# SLRC_2019_Robot_PCB_Schematic.net
KiCad netlist of a schematic drawn in Altium Designer
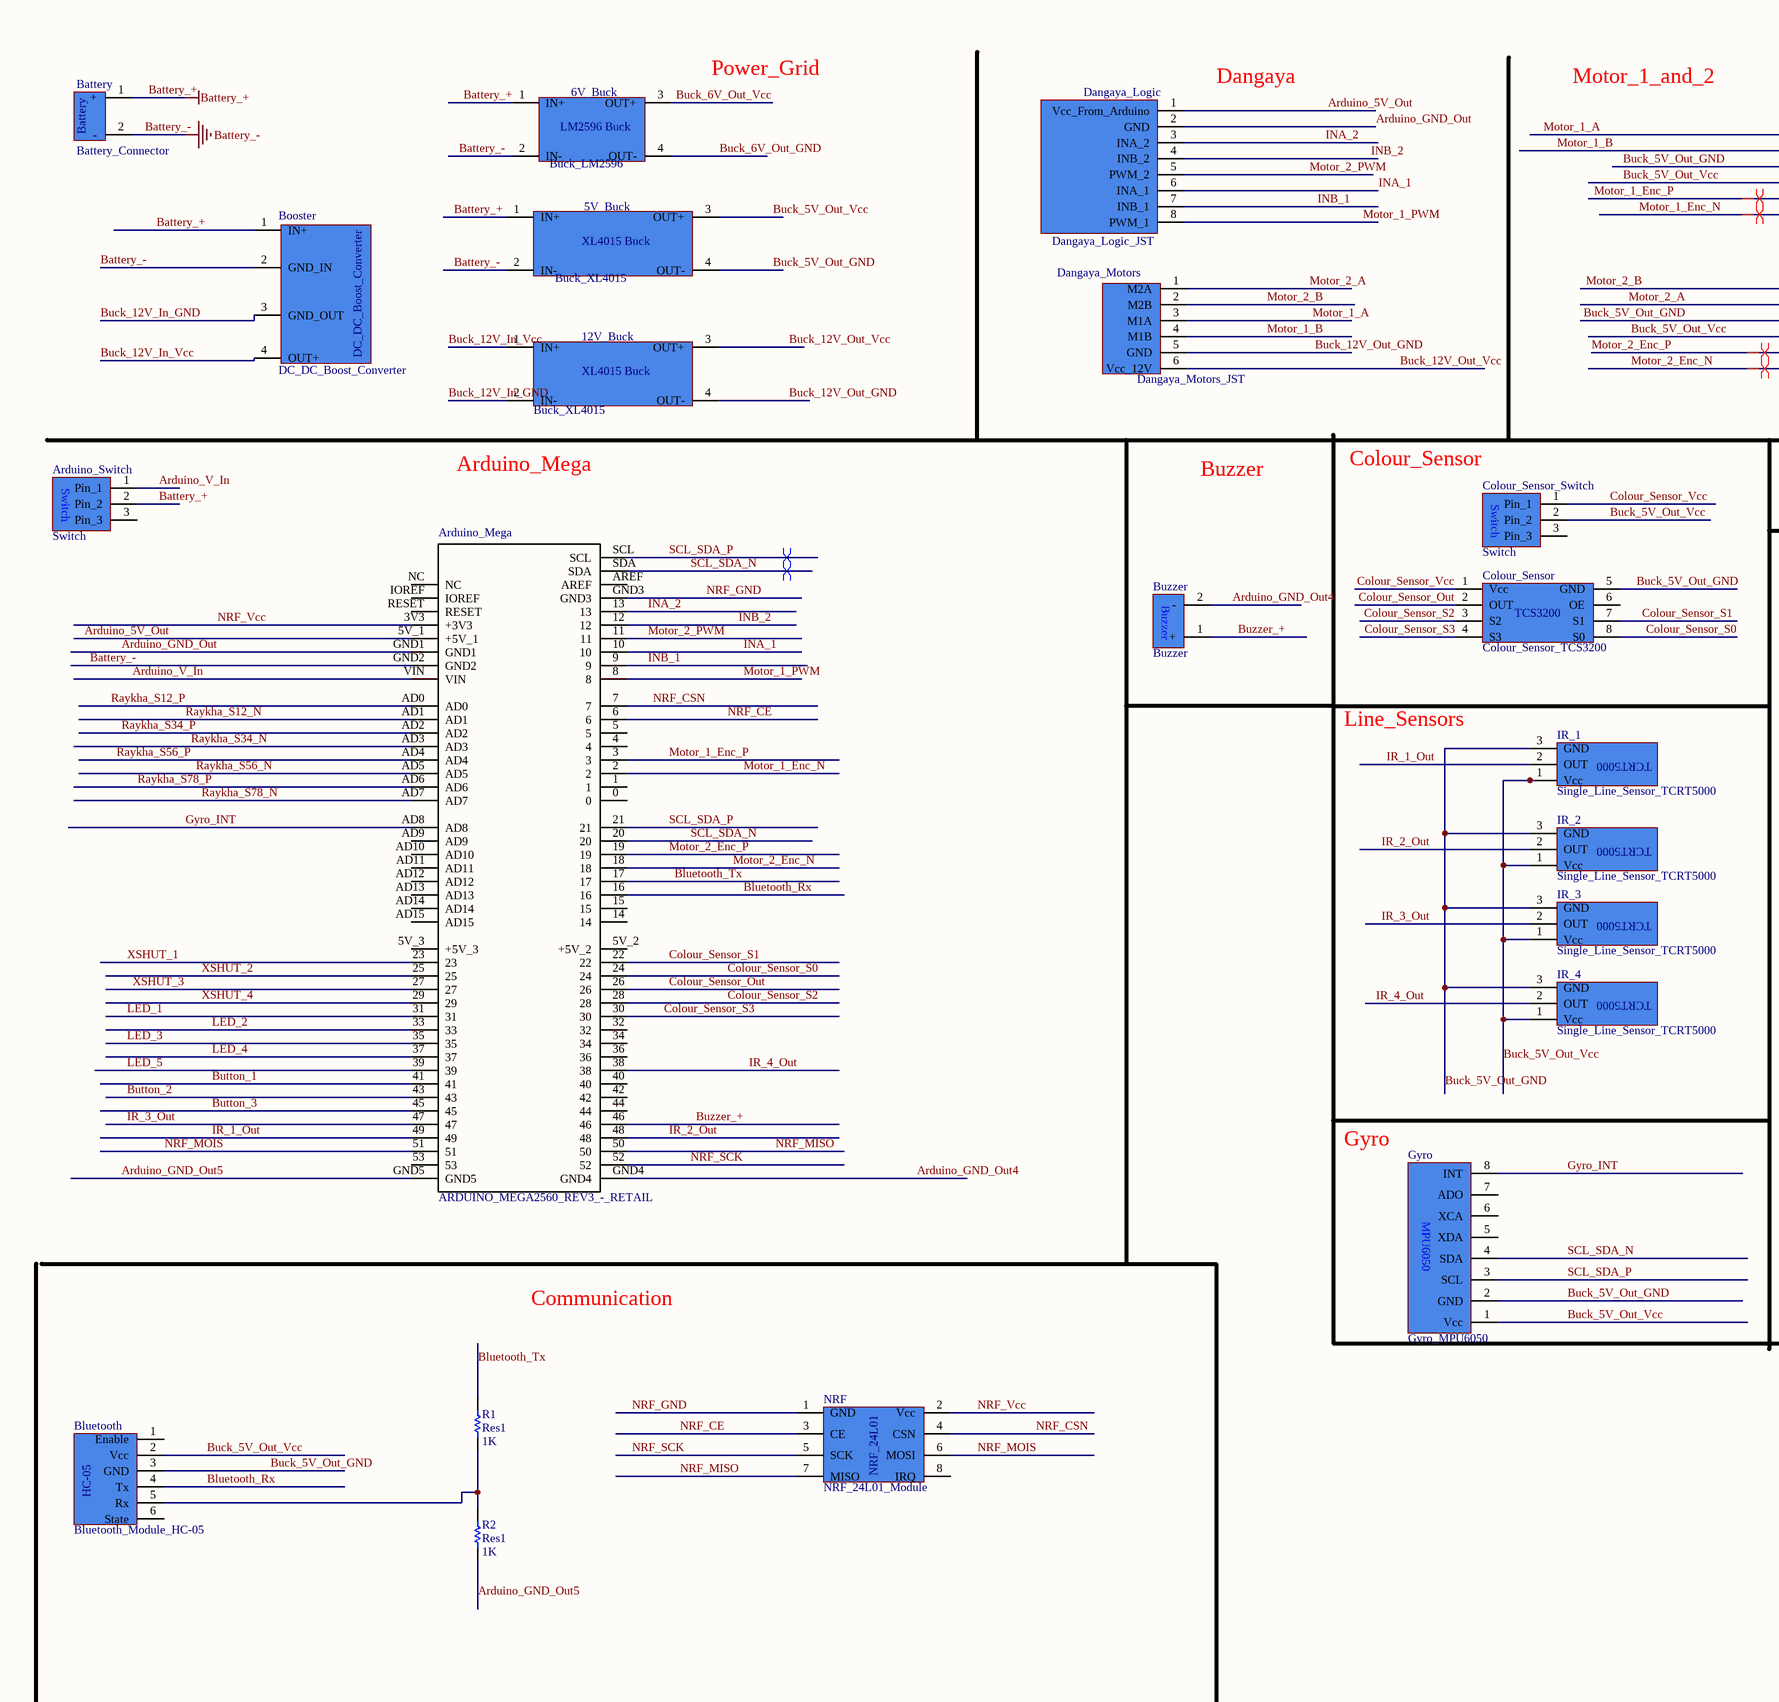
[diagram p0: SLRC_2019_Robot_PCB_Schematic.SchDoc, left]
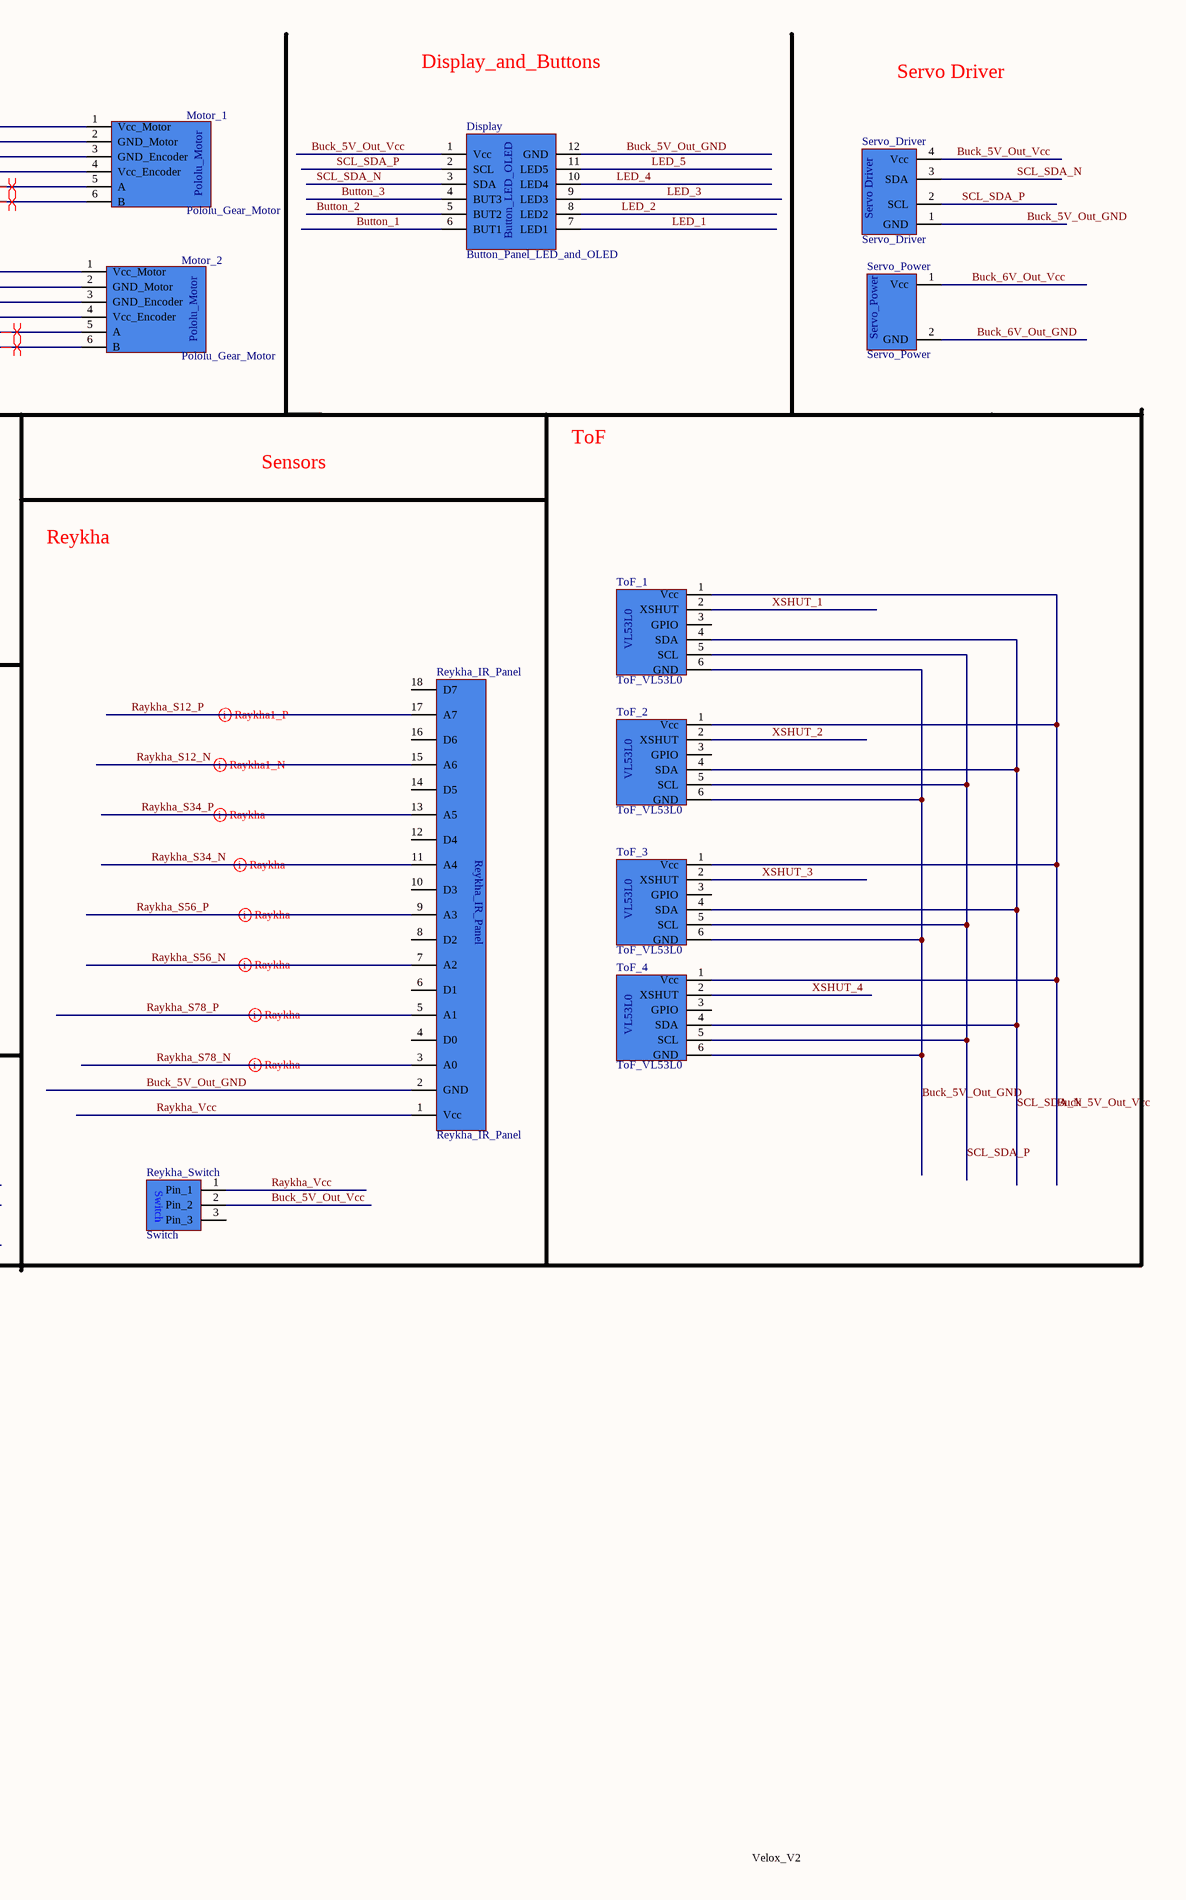
[diagram p1: SLRC_2019_Robot_PCB_Schematic.SchDoc, right]

(export (version "E")
  (design (tool "Eeschema 10.0.6"))
  (components
    (comp (ref "5V_Buck")
      (value "Buck_XL4015")
      (footprint "Buck_LM4015")
      (libsource (lib "SLRC_2019_Robot") (part "Buck_XL4015"))
    )
    (comp (ref "6V_Buck")
      (value "Buck_LM2596")
      (footprint "Buck_LM2596")
      (libsource (lib "SLRC_2019_Robot") (part "Buck_LM2596"))
    )
    (comp (ref "12V_Buck")
      (value "Buck_XL4015")
      (footprint "Buck_LM4015")
      (libsource (lib "SLRC_2019_Robot") (part "Buck_XL4015"))
    )
    (comp (ref "Arduino_Mega")
      (value "ARDUINO_MEGA2560_REV3_-_RETAIL")
      (footprint "*ARDUINO_MEGA2560_REV3_-_RETAIL_ARDUINO_MEGA2560_REV3_-_RETAIL(Primary)")
      (description "Dev.kit: Arduino; SPI, TWI, UART; ICSP, USB B, pin strips, supply")
      (fields (field (name "MF") "Arduino") (field (name "MP") "ARDUINO MEGA2560 REV3 - RETAIL"))
      (libsource (lib "ARDUINO_MEGA2560_REV3_-_RETAIL") (part "ARDUINO_MEGA2560_REV3_-_RETAIL"))
    )
    (comp (ref "Arduino_Switch")
      (value "Switch")
      (footprint "Switch")
      (libsource (lib "SLRC_2019_Robot") (part "Switch"))
    )
    (comp (ref "Battery")
      (value "Battery_Connector")
      (footprint "Battery_Connector")
      (libsource (lib "SLRC_2019_Robot") (part "Battery_Connector"))
    )
    (comp (ref "Bluetooth")
      (value "Bluetooth_Module_HC-05")
      (footprint "Bluetooth_Module_HC-05")
      (libsource (lib "SLRC_2019_Robot") (part "Bluetooth_Module_HC-05"))
    )
    (comp (ref "Booster")
      (value "DC_DC_Boost_Converter")
      (footprint "DC_DC_Boost_Converter")
      (libsource (lib "SLRC_2019_Robot") (part "DC_DC_Boost_Converter"))
    )
    (comp (ref "Buzzer")
      (value "Buzzer")
      (footprint "Buzzer")
      (libsource (lib "SLRC_2019_Robot") (part "Buzzer"))
    )
    (comp (ref "Colour_Sensor")
      (value "Colour_Sensor_TCS3200")
      (footprint "Colour_Sensor_TCS3200")
      (libsource (lib "SLRC_2019_Robot") (part "Colour_Sensor_TCS3200"))
    )
    (comp (ref "Colour_Sensor_Switch")
      (value "Switch")
      (footprint "Switch")
      (libsource (lib "SLRC_2019_Robot") (part "Switch"))
    )
    (comp (ref "Dangaya_Logic")
      (value "Dangaya_Logic_JST")
      (footprint "Dangaya_Logic_JST")
      (libsource (lib "SLRC_2019_Robot") (part "Dangaya_Logic_JST"))
    )
    (comp (ref "Dangaya_Motors")
      (value "Dangaya_Motors_JST")
      (footprint "Dangaya_Motors_JST")
      (libsource (lib "SLRC_2019_Robot") (part "Dangaya_Motors_JST"))
    )
    (comp (ref "Display")
      (value "Button_Panel_LED_and_OLED")
      (footprint "Button_Panel_LED_and_OLED")
      (libsource (lib "SLRC_2019_Robot") (part "Button_Panel_LED_and_OLED"))
    )
    (comp (ref "Gyro")
      (value "Gyro_MPU6050")
      (footprint "Gyro_MPU6050")
      (libsource (lib "SLRC_2019_Robot") (part "Gyro_MPU6050"))
    )
    (comp (ref "IR_1")
      (value "Single_Line_Sensor_TCRT5000")
      (footprint "Single_Line_Sensor_TCRT5000")
      (libsource (lib "SLRC_2019_Robot") (part "Single_Line_Sensor_TCRT5000"))
    )
    (comp (ref "IR_2")
      (value "Single_Line_Sensor_TCRT5000")
      (footprint "Single_Line_Sensor_TCRT5000")
      (libsource (lib "SLRC_2019_Robot") (part "Single_Line_Sensor_TCRT5000"))
    )
    (comp (ref "IR_3")
      (value "Single_Line_Sensor_TCRT5000")
      (footprint "Single_Line_Sensor_TCRT5000")
      (libsource (lib "SLRC_2019_Robot") (part "Single_Line_Sensor_TCRT5000"))
    )
    (comp (ref "IR_4")
      (value "Single_Line_Sensor_TCRT5000")
      (footprint "Single_Line_Sensor_TCRT5000")
      (libsource (lib "SLRC_2019_Robot") (part "Single_Line_Sensor_TCRT5000"))
    )
    (comp (ref "Motor_1")
      (value "Pololu_Gear_Motor")
      (footprint "Pololu_Gear_Motor")
      (libsource (lib "SLRC_2019_Robot") (part "Pololu_Gear_Motor"))
    )
    (comp (ref "Motor_2")
      (value "Pololu_Gear_Motor")
      (footprint "Pololu_Gear_Motor")
      (libsource (lib "SLRC_2019_Robot") (part "Pololu_Gear_Motor"))
    )
    (comp (ref "NRF")
      (value "NRF_24L01_Module")
      (footprint "NRF_24L01")
      (libsource (lib "SLRC_2019_Robot") (part "NRF_24L01_Module"))
    )
    (comp (ref "R1")
      (value "Res1")
      (footprint "AXIAL-0.3")
      (description "Resistor")
      (fields (field (name "ALTIUM_VALUE") "1K") (field (name "PUBLISHER") "Altium Limited"))
      (libsource (lib "Miscellaneous Devices") (part "Res1"))
    )
    (comp (ref "R2")
      (value "Res1")
      (footprint "AXIAL-0.3")
      (description "Resistor")
      (fields (field (name "ALTIUM_VALUE") "1K") (field (name "PUBLISHER") "Altium Limited"))
      (libsource (lib "Miscellaneous Devices") (part "Res1"))
    )
    (comp (ref "Reykha_IR_Panel")
      (value "Reykha_IR_Panel")
      (footprint "Reykha_IR_Panel")
      (libsource (lib "SLRC_2019_Robot") (part "Reykha_IR_Panel"))
    )
    (comp (ref "Reykha_Switch")
      (value "Switch")
      (footprint "Switch")
      (libsource (lib "SLRC_2019_Robot") (part "Switch"))
    )
    (comp (ref "Servo_Driver")
      (value "Servo_Driver")
      (footprint "Servo_Driver")
      (libsource (lib "SLRC_2019_Robot") (part "Servo_Driver"))
    )
    (comp (ref "Servo_Power")
      (value "Servo_Power")
      (footprint "Servo_Power")
      (libsource (lib "SLRC_2019_Robot") (part "Servo_Power"))
    )
    (comp (ref "ToF_1")
      (value "ToF_VL53L0")
      (footprint "ToF_VL53L0")
      (libsource (lib "SLRC_2019_Robot") (part "ToF_VL53L0"))
    )
    (comp (ref "ToF_2")
      (value "ToF_VL53L0")
      (footprint "ToF_VL53L0")
      (libsource (lib "SLRC_2019_Robot") (part "ToF_VL53L0"))
    )
    (comp (ref "ToF_3")
      (value "ToF_VL53L0")
      (footprint "ToF_VL53L0")
      (libsource (lib "SLRC_2019_Robot") (part "ToF_VL53L0"))
    )
    (comp (ref "ToF_4")
      (value "ToF_VL53L0")
      (footprint "ToF_VL53L0")
      (libsource (lib "SLRC_2019_Robot") (part "ToF_VL53L0"))
    )
  )
  (nets
    (net (code "1") (name "/Arduino_5V_Out") (class "Default")
      (node (ref "Arduino_Mega") (pin "5V_1") (pinfunction "+5V_1_5V_1") (pintype "passive"))
      (node (ref "Dangaya_Logic") (pin "1") (pinfunction "Vcc_From_Arduino_1") (pintype "power_in"))
    )
    (net (code "2") (name "/Arduino_GND_Out") (class "Default")
      (node (ref "Arduino_Mega") (pin "GND1") (pinfunction "GND1_GND1") (pintype "passive"))
      (node (ref "Dangaya_Logic") (pin "2") (pinfunction "GND_2") (pintype "power_in"))
    )
    (net (code "3") (name "/Arduino_GND_Out4") (class "Default")
      (node (ref "Arduino_Mega") (pin "GND4") (pinfunction "GND4_GND4") (pintype "passive"))
      (node (ref "Buzzer") (pin "2") (pinfunction "-_2") (pintype "passive"))
    )
    (net (code "4") (name "/Arduino_GND_Out5") (class "Default")
      (node (ref "Arduino_Mega") (pin "GND5") (pinfunction "GND5_GND5") (pintype "passive"))
      (node (ref "R2") (pin "1") (pinfunction "1_1") (pintype "passive"))
    )
    (net (code "5") (name "/Arduino_V_In") (class "Default")
      (node (ref "Arduino_Mega") (pin "VIN") (pinfunction "VIN_VIN") (pintype "passive"))
      (node (ref "Arduino_Switch") (pin "1") (pinfunction "Pin_1_1") (pintype "power_in"))
    )
    (net (code "6") (name "/Bluetooth_Rx") (class "Default")
      (node (ref "Arduino_Mega") (pin "16") (pinfunction "16_16") (pintype "passive"))
      (node (ref "Bluetooth") (pin "4") (pinfunction "Tx_4") (pintype "passive"))
    )
    (net (code "7") (name "/Bluetooth_Tx") (class "Default")
      (node (ref "Arduino_Mega") (pin "17") (pinfunction "17_17") (pintype "passive"))
      (node (ref "R1") (pin "2") (pinfunction "2_2") (pintype "passive"))
    )
    (net (code "8") (name "/Buck_5V_Out_GND") (class "Default")
      (node (ref "5V_Buck") (pin "4") (pinfunction "OUT-_4") (pintype "power_in"))
      (node (ref "Bluetooth") (pin "3") (pinfunction "GND_3") (pintype "power_in"))
      (node (ref "Colour_Sensor") (pin "5") (pinfunction "GND_5") (pintype "power_in"))
      (node (ref "Display") (pin "12") (pinfunction "GND_12") (pintype "power_in"))
      (node (ref "Gyro") (pin "2") (pinfunction "GND_2") (pintype "power_in"))
      (node (ref "IR_1") (pin "3") (pinfunction "GND_3") (pintype "power_in"))
      (node (ref "IR_2") (pin "3") (pinfunction "GND_3") (pintype "power_in"))
      (node (ref "IR_3") (pin "3") (pinfunction "GND_3") (pintype "power_in"))
      (node (ref "IR_4") (pin "3") (pinfunction "GND_3") (pintype "power_in"))
      (node (ref "Motor_1") (pin "3") (pinfunction "GND_Encoder_3") (pintype "power_in"))
      (node (ref "Motor_2") (pin "3") (pinfunction "GND_Encoder_3") (pintype "power_in"))
      (node (ref "Reykha_IR_Panel") (pin "2") (pinfunction "GND_2") (pintype "power_in"))
      (node (ref "Servo_Driver") (pin "1") (pinfunction "GND_1") (pintype "power_in"))
      (node (ref "ToF_1") (pin "6") (pinfunction "GND_6") (pintype "power_in"))
      (node (ref "ToF_2") (pin "6") (pinfunction "GND_6") (pintype "power_in"))
      (node (ref "ToF_3") (pin "6") (pinfunction "GND_6") (pintype "power_in"))
      (node (ref "ToF_4") (pin "6") (pinfunction "GND_6") (pintype "power_in"))
    )
    (net (code "9") (name "/Buck_5V_Out_Vcc") (class "Default")
      (node (ref "5V_Buck") (pin "3") (pinfunction "OUT+_3") (pintype "power_in"))
      (node (ref "Bluetooth") (pin "2") (pinfunction "Vcc_2") (pintype "power_in"))
      (node (ref "Colour_Sensor_Switch") (pin "2") (pinfunction "Pin_2_2") (pintype "power_in"))
      (node (ref "Display") (pin "1") (pinfunction "Vcc_1") (pintype "power_in"))
      (node (ref "Gyro") (pin "1") (pinfunction "Vcc_1") (pintype "power_in"))
      (node (ref "IR_1") (pin "1") (pinfunction "Vcc_1") (pintype "power_in"))
      (node (ref "IR_2") (pin "1") (pinfunction "Vcc_1") (pintype "power_in"))
      (node (ref "IR_3") (pin "1") (pinfunction "Vcc_1") (pintype "power_in"))
      (node (ref "IR_4") (pin "1") (pinfunction "Vcc_1") (pintype "power_in"))
      (node (ref "Motor_1") (pin "4") (pinfunction "Vcc_Encoder_4") (pintype "power_in"))
      (node (ref "Motor_2") (pin "4") (pinfunction "Vcc_Encoder_4") (pintype "power_in"))
      (node (ref "Reykha_Switch") (pin "2") (pinfunction "Pin_2_2") (pintype "power_in"))
      (node (ref "Servo_Driver") (pin "4") (pinfunction "Vcc_4") (pintype "power_in"))
      (node (ref "ToF_1") (pin "1") (pinfunction "Vcc_1") (pintype "power_in"))
      (node (ref "ToF_2") (pin "1") (pinfunction "Vcc_1") (pintype "power_in"))
      (node (ref "ToF_3") (pin "1") (pinfunction "Vcc_1") (pintype "power_in"))
      (node (ref "ToF_4") (pin "1") (pinfunction "Vcc_1") (pintype "power_in"))
    )
    (net (code "10") (name "/Buck_6V_Out_GND") (class "Default")
      (node (ref "6V_Buck") (pin "4") (pinfunction "OUT-_4") (pintype "power_in"))
      (node (ref "Servo_Power") (pin "2") (pinfunction "GND_2") (pintype "power_in"))
    )
    (net (code "11") (name "/Buck_6V_Out_Vcc") (class "Default")
      (node (ref "6V_Buck") (pin "3") (pinfunction "OUT+_3") (pintype "power_in"))
      (node (ref "Servo_Power") (pin "1") (pinfunction "Vcc_1") (pintype "power_in"))
    )
    (net (code "12") (name "/Buck_12V_In_GND") (class "Default")
      (node (ref "12V_Buck") (pin "2") (pinfunction "IN-_2") (pintype "power_in"))
      (node (ref "Booster") (pin "3") (pinfunction "GND_OUT_3") (pintype "power_in"))
    )
    (net (code "13") (name "/Buck_12V_In_Vcc") (class "Default")
      (node (ref "12V_Buck") (pin "1") (pinfunction "IN+_1") (pintype "power_in"))
      (node (ref "Booster") (pin "4") (pinfunction "OUT+_4") (pintype "power_in"))
    )
    (net (code "14") (name "/Buck_12V_Out_GND") (class "Default")
      (node (ref "12V_Buck") (pin "4") (pinfunction "OUT-_4") (pintype "power_in"))
      (node (ref "Dangaya_Motors") (pin "5") (pinfunction "GND_5") (pintype "power_in"))
    )
    (net (code "15") (name "/Buck_12V_Out_Vcc") (class "Default")
      (node (ref "12V_Buck") (pin "3") (pinfunction "OUT+_3") (pintype "power_in"))
      (node (ref "Dangaya_Motors") (pin "6") (pinfunction "Vcc_12V_6") (pintype "power_in"))
    )
    (net (code "16") (name "/Button_1") (class "Default")
      (node (ref "Arduino_Mega") (pin "41") (pinfunction "41_41") (pintype "passive"))
      (node (ref "Display") (pin "6") (pinfunction "BUT1_6") (pintype "passive"))
    )
    (net (code "17") (name "/Button_2") (class "Default")
      (node (ref "Arduino_Mega") (pin "43") (pinfunction "43_43") (pintype "passive"))
      (node (ref "Display") (pin "5") (pinfunction "BUT2_5") (pintype "passive"))
    )
    (net (code "18") (name "/Button_3") (class "Default")
      (node (ref "Arduino_Mega") (pin "45") (pinfunction "45_45") (pintype "passive"))
      (node (ref "Display") (pin "4") (pinfunction "BUT3_4") (pintype "passive"))
    )
    (net (code "19") (name "/Buzzer_+") (class "Default")
      (node (ref "Arduino_Mega") (pin "46") (pinfunction "46_46") (pintype "passive"))
      (node (ref "Buzzer") (pin "1") (pinfunction "+_1") (pintype "passive"))
    )
    (net (code "20") (name "/Colour_Sensor_Out") (class "Default")
      (node (ref "Arduino_Mega") (pin "26") (pinfunction "26_26") (pintype "passive"))
      (node (ref "Colour_Sensor") (pin "2") (pinfunction "OUT_2") (pintype "passive"))
    )
    (net (code "21") (name "/Colour_Sensor_S0") (class "Default")
      (node (ref "Arduino_Mega") (pin "24") (pinfunction "24_24") (pintype "passive"))
      (node (ref "Colour_Sensor") (pin "8") (pinfunction "S0_8") (pintype "passive"))
    )
    (net (code "22") (name "/Colour_Sensor_S1") (class "Default")
      (node (ref "Arduino_Mega") (pin "22") (pinfunction "22_22") (pintype "passive"))
      (node (ref "Colour_Sensor") (pin "7") (pinfunction "S1_7") (pintype "passive"))
    )
    (net (code "23") (name "/Colour_Sensor_S2") (class "Default")
      (node (ref "Arduino_Mega") (pin "28") (pinfunction "28_28") (pintype "passive"))
      (node (ref "Colour_Sensor") (pin "3") (pinfunction "S2_3") (pintype "passive"))
    )
    (net (code "24") (name "/Colour_Sensor_S3") (class "Default")
      (node (ref "Arduino_Mega") (pin "30") (pinfunction "30_30") (pintype "passive"))
      (node (ref "Colour_Sensor") (pin "4") (pinfunction "S3_4") (pintype "passive"))
    )
    (net (code "25") (name "/Colour_Sensor_Vcc") (class "Default")
      (node (ref "Colour_Sensor") (pin "1") (pinfunction "Vcc_1") (pintype "power_in"))
      (node (ref "Colour_Sensor_Switch") (pin "1") (pinfunction "Pin_1_1") (pintype "power_in"))
    )
    (net (code "26") (name "/Gyro_INT") (class "Default")
      (node (ref "Arduino_Mega") (pin "AD8") (pinfunction "AD8_AD8") (pintype "passive"))
      (node (ref "Gyro") (pin "8") (pinfunction "INT_8") (pintype "passive"))
    )
    (net (code "27") (name "/INA_1") (class "Default")
      (node (ref "Arduino_Mega") (pin "10") (pinfunction "10_10") (pintype "passive"))
      (node (ref "Dangaya_Logic") (pin "6") (pinfunction "INA_1_6") (pintype "passive"))
    )
    (net (code "28") (name "/INA_2") (class "Default")
      (node (ref "Arduino_Mega") (pin "13") (pinfunction "13_13") (pintype "passive"))
      (node (ref "Dangaya_Logic") (pin "3") (pinfunction "INA_2_3") (pintype "passive"))
    )
    (net (code "29") (name "/INB_1") (class "Default")
      (node (ref "Arduino_Mega") (pin "9") (pinfunction "9_9") (pintype "passive"))
      (node (ref "Dangaya_Logic") (pin "7") (pinfunction "INB_1_7") (pintype "passive"))
    )
    (net (code "30") (name "/INB_2") (class "Default")
      (node (ref "Arduino_Mega") (pin "12") (pinfunction "12_12") (pintype "passive"))
      (node (ref "Dangaya_Logic") (pin "4") (pinfunction "INB_2_4") (pintype "passive"))
    )
    (net (code "31") (name "/IR_1_Out") (class "Default")
      (node (ref "Arduino_Mega") (pin "49") (pinfunction "49_49") (pintype "passive"))
      (node (ref "IR_1") (pin "2") (pinfunction "OUT_2") (pintype "passive"))
    )
    (net (code "32") (name "/IR_2_Out") (class "Default")
      (node (ref "Arduino_Mega") (pin "48") (pinfunction "48_48") (pintype "passive"))
      (node (ref "IR_2") (pin "2") (pinfunction "OUT_2") (pintype "passive"))
    )
    (net (code "33") (name "/IR_3_Out") (class "Default")
      (node (ref "Arduino_Mega") (pin "47") (pinfunction "47_47") (pintype "passive"))
      (node (ref "IR_3") (pin "2") (pinfunction "OUT_2") (pintype "passive"))
    )
    (net (code "34") (name "/IR_4_Out") (class "Default")
      (node (ref "Arduino_Mega") (pin "38") (pinfunction "38_38") (pintype "passive"))
      (node (ref "IR_4") (pin "2") (pinfunction "OUT_2") (pintype "passive"))
    )
    (net (code "35") (name "/LED_1") (class "Default")
      (node (ref "Arduino_Mega") (pin "31") (pinfunction "31_31") (pintype "passive"))
      (node (ref "Display") (pin "7") (pinfunction "LED1_7") (pintype "passive"))
    )
    (net (code "36") (name "/LED_2") (class "Default")
      (node (ref "Arduino_Mega") (pin "33") (pinfunction "33_33") (pintype "passive"))
      (node (ref "Display") (pin "8") (pinfunction "LED2_8") (pintype "passive"))
    )
    (net (code "37") (name "/LED_3") (class "Default")
      (node (ref "Arduino_Mega") (pin "35") (pinfunction "35_35") (pintype "passive"))
      (node (ref "Display") (pin "9") (pinfunction "LED3_9") (pintype "passive"))
    )
    (net (code "38") (name "/LED_4") (class "Default")
      (node (ref "Arduino_Mega") (pin "37") (pinfunction "37_37") (pintype "passive"))
      (node (ref "Display") (pin "10") (pinfunction "LED4_10") (pintype "passive"))
    )
    (net (code "39") (name "/LED_5") (class "Default")
      (node (ref "Arduino_Mega") (pin "39") (pinfunction "39_39") (pintype "passive"))
      (node (ref "Display") (pin "11") (pinfunction "LED5_11") (pintype "passive"))
    )
    (net (code "40") (name "/Motor_1_A") (class "Default")
      (node (ref "Dangaya_Motors") (pin "3") (pinfunction "M1A_3") (pintype "passive"))
      (node (ref "Motor_1") (pin "1") (pinfunction "Vcc_Motor_1") (pintype "power_in"))
    )
    (net (code "41") (name "/Motor_1_B") (class "Default")
      (node (ref "Dangaya_Motors") (pin "4") (pinfunction "M1B_4") (pintype "passive"))
      (node (ref "Motor_1") (pin "2") (pinfunction "GND_Motor_2") (pintype "power_in"))
    )
    (net (code "42") (name "/Motor_1_Enc_N") (class "Default")
      (node (ref "Arduino_Mega") (pin "2") (pinfunction "2_2") (pintype "passive"))
      (node (ref "Motor_1") (pin "6") (pinfunction "B_6") (pintype "passive"))
    )
    (net (code "43") (name "/Motor_1_Enc_P") (class "Default")
      (node (ref "Arduino_Mega") (pin "3") (pinfunction "3_3") (pintype "passive"))
      (node (ref "Motor_1") (pin "5") (pinfunction "A_5") (pintype "passive"))
    )
    (net (code "44") (name "/Motor_1_PWM") (class "Default")
      (node (ref "Arduino_Mega") (pin "8") (pinfunction "8_8") (pintype "passive"))
      (node (ref "Dangaya_Logic") (pin "8") (pinfunction "PWM_1_8") (pintype "passive"))
    )
    (net (code "45") (name "/Motor_2_A") (class "Default")
      (node (ref "Dangaya_Motors") (pin "1") (pinfunction "M2A_1") (pintype "passive"))
      (node (ref "Motor_2") (pin "2") (pinfunction "GND_Motor_2") (pintype "power_in"))
    )
    (net (code "46") (name "/Motor_2_B") (class "Default")
      (node (ref "Dangaya_Motors") (pin "2") (pinfunction "M2B_2") (pintype "passive"))
      (node (ref "Motor_2") (pin "1") (pinfunction "Vcc_Motor_1") (pintype "power_in"))
    )
    (net (code "47") (name "/Motor_2_Enc_N") (class "Default")
      (node (ref "Arduino_Mega") (pin "18") (pinfunction "18_18") (pintype "passive"))
      (node (ref "Motor_2") (pin "6") (pinfunction "B_6") (pintype "passive"))
    )
    (net (code "48") (name "/Motor_2_Enc_P") (class "Default")
      (node (ref "Arduino_Mega") (pin "19") (pinfunction "19_19") (pintype "passive"))
      (node (ref "Motor_2") (pin "5") (pinfunction "A_5") (pintype "passive"))
    )
    (net (code "49") (name "/Motor_2_PWM") (class "Default")
      (node (ref "Arduino_Mega") (pin "11") (pinfunction "11_11") (pintype "passive"))
      (node (ref "Dangaya_Logic") (pin "5") (pinfunction "PWM_2_5") (pintype "passive"))
    )
    (net (code "50") (name "/NRF_CE") (class "Default")
      (node (ref "Arduino_Mega") (pin "6") (pinfunction "6_6") (pintype "passive"))
      (node (ref "NRF") (pin "3") (pinfunction "CE_3") (pintype "passive"))
    )
    (net (code "51") (name "/NRF_CSN") (class "Default")
      (node (ref "Arduino_Mega") (pin "7") (pinfunction "7_7") (pintype "passive"))
      (node (ref "NRF") (pin "4") (pinfunction "CSN_4") (pintype "passive"))
    )
    (net (code "52") (name "/NRF_GND") (class "Default")
      (node (ref "Arduino_Mega") (pin "GND3") (pinfunction "GND3_GND3") (pintype "passive"))
      (node (ref "NRF") (pin "1") (pinfunction "GND_1") (pintype "power_in"))
    )
    (net (code "53") (name "/NRF_MISO") (class "Default")
      (node (ref "Arduino_Mega") (pin "50") (pinfunction "50_50") (pintype "passive"))
      (node (ref "NRF") (pin "7") (pinfunction "MISO_7") (pintype "passive"))
    )
    (net (code "54") (name "/NRF_MOIS") (class "Default")
      (node (ref "Arduino_Mega") (pin "51") (pinfunction "51_51") (pintype "passive"))
      (node (ref "NRF") (pin "6") (pinfunction "MOSI_6") (pintype "passive"))
    )
    (net (code "55") (name "/NRF_SCK") (class "Default")
      (node (ref "Arduino_Mega") (pin "52") (pinfunction "52_52") (pintype "passive"))
      (node (ref "NRF") (pin "5") (pinfunction "SCK_5") (pintype "passive"))
    )
    (net (code "56") (name "/NRF_Vcc") (class "Default")
      (node (ref "Arduino_Mega") (pin "3V3") (pinfunction "+3V3_3V3") (pintype "passive"))
      (node (ref "NRF") (pin "2") (pinfunction "Vcc_2") (pintype "power_in"))
    )
    (net (code "57") (name "/Raykha_S12_N") (class "Default")
      (node (ref "Arduino_Mega") (pin "AD1") (pinfunction "AD1_AD1") (pintype "passive"))
      (node (ref "Reykha_IR_Panel") (pin "15") (pinfunction "A6_15") (pintype "passive"))
    )
    (net (code "58") (name "/Raykha_S12_P") (class "Default")
      (node (ref "Arduino_Mega") (pin "AD0") (pinfunction "AD0_AD0") (pintype "passive"))
      (node (ref "Reykha_IR_Panel") (pin "17") (pinfunction "A7_17") (pintype "passive"))
    )
    (net (code "59") (name "/Raykha_S34_N") (class "Default")
      (node (ref "Arduino_Mega") (pin "AD3") (pinfunction "AD3_AD3") (pintype "passive"))
      (node (ref "Reykha_IR_Panel") (pin "11") (pinfunction "A4_11") (pintype "passive"))
    )
    (net (code "60") (name "/Raykha_S34_P") (class "Default")
      (node (ref "Arduino_Mega") (pin "AD2") (pinfunction "AD2_AD2") (pintype "passive"))
      (node (ref "Reykha_IR_Panel") (pin "13") (pinfunction "A5_13") (pintype "passive"))
    )
    (net (code "61") (name "/Raykha_S56_N") (class "Default")
      (node (ref "Arduino_Mega") (pin "AD5") (pinfunction "AD5_AD5") (pintype "passive"))
      (node (ref "Reykha_IR_Panel") (pin "7") (pinfunction "A2_7") (pintype "passive"))
    )
    (net (code "62") (name "/Raykha_S56_P") (class "Default")
      (node (ref "Arduino_Mega") (pin "AD4") (pinfunction "AD4_AD4") (pintype "passive"))
      (node (ref "Reykha_IR_Panel") (pin "9") (pinfunction "A3_9") (pintype "passive"))
    )
    (net (code "63") (name "/Raykha_S78_N") (class "Default")
      (node (ref "Arduino_Mega") (pin "AD7") (pinfunction "AD7_AD7") (pintype "passive"))
      (node (ref "Reykha_IR_Panel") (pin "3") (pinfunction "A0_3") (pintype "passive"))
    )
    (net (code "64") (name "/Raykha_S78_P") (class "Default")
      (node (ref "Arduino_Mega") (pin "AD6") (pinfunction "AD6_AD6") (pintype "passive"))
      (node (ref "Reykha_IR_Panel") (pin "5") (pinfunction "A1_5") (pintype "passive"))
    )
    (net (code "65") (name "/Raykha_Vcc") (class "Default")
      (node (ref "Reykha_IR_Panel") (pin "1") (pinfunction "Vcc_1") (pintype "power_in"))
      (node (ref "Reykha_Switch") (pin "1") (pinfunction "Pin_1_1") (pintype "power_in"))
    )
    (net (code "66") (name "/SCL_SDA_N") (class "Default")
      (node (ref "Arduino_Mega") (pin "20") (pinfunction "20_20") (pintype "passive"))
      (node (ref "Arduino_Mega") (pin "SDA") (pinfunction "SDA_SDA") (pintype "passive"))
      (node (ref "Display") (pin "3") (pinfunction "SDA_3") (pintype "passive"))
      (node (ref "Gyro") (pin "4") (pinfunction "SDA_4") (pintype "passive"))
      (node (ref "Servo_Driver") (pin "3") (pinfunction "SDA_3") (pintype "passive"))
      (node (ref "ToF_1") (pin "4") (pinfunction "SDA_4") (pintype "passive"))
      (node (ref "ToF_2") (pin "4") (pinfunction "SDA_4") (pintype "passive"))
      (node (ref "ToF_3") (pin "4") (pinfunction "SDA_4") (pintype "passive"))
      (node (ref "ToF_4") (pin "4") (pinfunction "SDA_4") (pintype "passive"))
    )
    (net (code "67") (name "/SCL_SDA_P") (class "Default")
      (node (ref "Arduino_Mega") (pin "21") (pinfunction "21_21") (pintype "passive"))
      (node (ref "Arduino_Mega") (pin "SCL") (pinfunction "SCL_SCL") (pintype "passive"))
      (node (ref "Display") (pin "2") (pinfunction "SCL_2") (pintype "passive"))
      (node (ref "Gyro") (pin "3") (pinfunction "SCL_3") (pintype "passive"))
      (node (ref "Servo_Driver") (pin "2") (pinfunction "SCL_2") (pintype "passive"))
      (node (ref "ToF_1") (pin "5") (pinfunction "SCL_5") (pintype "passive"))
      (node (ref "ToF_2") (pin "5") (pinfunction "SCL_5") (pintype "passive"))
      (node (ref "ToF_3") (pin "5") (pinfunction "SCL_5") (pintype "passive"))
      (node (ref "ToF_4") (pin "5") (pinfunction "SCL_5") (pintype "passive"))
    )
    (net (code "68") (name "/XSHUT_1") (class "Default")
      (node (ref "Arduino_Mega") (pin "23") (pinfunction "23_23") (pintype "passive"))
      (node (ref "ToF_1") (pin "2") (pinfunction "XSHUT_2") (pintype "passive"))
    )
    (net (code "69") (name "/XSHUT_2") (class "Default")
      (node (ref "Arduino_Mega") (pin "25") (pinfunction "25_25") (pintype "passive"))
      (node (ref "ToF_2") (pin "2") (pinfunction "XSHUT_2") (pintype "passive"))
    )
    (net (code "70") (name "/XSHUT_3") (class "Default")
      (node (ref "Arduino_Mega") (pin "27") (pinfunction "27_27") (pintype "passive"))
      (node (ref "ToF_3") (pin "2") (pinfunction "XSHUT_2") (pintype "passive"))
    )
    (net (code "71") (name "/XSHUT_4") (class "Default")
      (node (ref "Arduino_Mega") (pin "29") (pinfunction "29_29") (pintype "passive"))
      (node (ref "ToF_4") (pin "2") (pinfunction "XSHUT_2") (pintype "passive"))
    )
    (net (code "72") (name "Battery_+") (class "Default")
      (node (ref "5V_Buck") (pin "1") (pinfunction "IN+_1") (pintype "power_in"))
      (node (ref "6V_Buck") (pin "1") (pinfunction "IN+_1") (pintype "power_in"))
      (node (ref "Arduino_Switch") (pin "2") (pinfunction "Pin_2_2") (pintype "power_in"))
      (node (ref "Battery") (pin "1") (pinfunction "+_1") (pintype "power_in"))
      (node (ref "Booster") (pin "1") (pinfunction "IN+_1") (pintype "power_in"))
    )
    (net (code "73") (name "Battery_-") (class "Default")
      (node (ref "5V_Buck") (pin "2") (pinfunction "IN-_2") (pintype "power_in"))
      (node (ref "6V_Buck") (pin "2") (pinfunction "IN-_2") (pintype "power_in"))
      (node (ref "Arduino_Mega") (pin "GND2") (pinfunction "GND2_GND2") (pintype "passive"))
      (node (ref "Battery") (pin "2") (pinfunction "-_2") (pintype "power_in"))
      (node (ref "Booster") (pin "2") (pinfunction "GND_IN_2") (pintype "power_in"))
    )
    (net (code "74") (name "Net-(Bluetooth-Rx)") (class "Default")
      (node (ref "Bluetooth") (pin "5") (pinfunction "Rx_5") (pintype "passive"))
      (node (ref "R1") (pin "1") (pinfunction "1_1") (pintype "passive"))
      (node (ref "R2") (pin "2") (pinfunction "2_2") (pintype "passive"))
    )
    (net (code "75") (name "unconnected-(Arduino_Mega-+5V_2-Pad5V_2)") (class "Default")
      (node (ref "Arduino_Mega") (pin "5V_2") (pinfunction "+5V_2_5V_2") (pintype "passive"))
    )
    (net (code "76") (name "unconnected-(Arduino_Mega-+5V_3-Pad5V_3)") (class "Default")
      (node (ref "Arduino_Mega") (pin "5V_3") (pinfunction "+5V_3_5V_3") (pintype "passive"))
    )
    (net (code "77") (name "unconnected-(Arduino_Mega-Pad0)") (class "Default")
      (node (ref "Arduino_Mega") (pin "0") (pinfunction "0_0") (pintype "passive"))
    )
    (net (code "78") (name "unconnected-(Arduino_Mega-Pad1)") (class "Default")
      (node (ref "Arduino_Mega") (pin "1") (pinfunction "1_1") (pintype "passive"))
    )
    (net (code "79") (name "unconnected-(Arduino_Mega-Pad4)") (class "Default")
      (node (ref "Arduino_Mega") (pin "4") (pinfunction "4_4") (pintype "passive"))
    )
    (net (code "80") (name "unconnected-(Arduino_Mega-Pad5)") (class "Default")
      (node (ref "Arduino_Mega") (pin "5") (pinfunction "5_5") (pintype "passive"))
    )
    (net (code "81") (name "unconnected-(Arduino_Mega-Pad14)") (class "Default")
      (node (ref "Arduino_Mega") (pin "14") (pinfunction "14_14") (pintype "passive"))
    )
    (net (code "82") (name "unconnected-(Arduino_Mega-Pad15)") (class "Default")
      (node (ref "Arduino_Mega") (pin "15") (pinfunction "15_15") (pintype "passive"))
    )
    (net (code "83") (name "unconnected-(Arduino_Mega-Pad32)") (class "Default")
      (node (ref "Arduino_Mega") (pin "32") (pinfunction "32_32") (pintype "passive"))
    )
    (net (code "84") (name "unconnected-(Arduino_Mega-Pad34)") (class "Default")
      (node (ref "Arduino_Mega") (pin "34") (pinfunction "34_34") (pintype "passive"))
    )
    (net (code "85") (name "unconnected-(Arduino_Mega-Pad36)") (class "Default")
      (node (ref "Arduino_Mega") (pin "36") (pinfunction "36_36") (pintype "passive"))
    )
    (net (code "86") (name "unconnected-(Arduino_Mega-Pad40)") (class "Default")
      (node (ref "Arduino_Mega") (pin "40") (pinfunction "40_40") (pintype "passive"))
    )
    (net (code "87") (name "unconnected-(Arduino_Mega-Pad42)") (class "Default")
      (node (ref "Arduino_Mega") (pin "42") (pinfunction "42_42") (pintype "passive"))
    )
    (net (code "88") (name "unconnected-(Arduino_Mega-Pad44)") (class "Default")
      (node (ref "Arduino_Mega") (pin "44") (pinfunction "44_44") (pintype "passive"))
    )
    (net (code "89") (name "unconnected-(Arduino_Mega-Pad53)") (class "Default")
      (node (ref "Arduino_Mega") (pin "53") (pinfunction "53_53") (pintype "passive"))
    )
    (net (code "90") (name "unconnected-(Arduino_Mega-PadAD9)") (class "Default")
      (node (ref "Arduino_Mega") (pin "AD9") (pinfunction "AD9_AD9") (pintype "passive"))
    )
    (net (code "91") (name "unconnected-(Arduino_Mega-PadAD10)") (class "Default")
      (node (ref "Arduino_Mega") (pin "AD10") (pinfunction "AD10_AD10") (pintype "passive"))
    )
    (net (code "92") (name "unconnected-(Arduino_Mega-PadAD11)") (class "Default")
      (node (ref "Arduino_Mega") (pin "AD11") (pinfunction "AD11_AD11") (pintype "passive"))
    )
    (net (code "93") (name "unconnected-(Arduino_Mega-PadAD12)") (class "Default")
      (node (ref "Arduino_Mega") (pin "AD12") (pinfunction "AD12_AD12") (pintype "passive"))
    )
    (net (code "94") (name "unconnected-(Arduino_Mega-PadAD13)") (class "Default")
      (node (ref "Arduino_Mega") (pin "AD13") (pinfunction "AD13_AD13") (pintype "passive"))
    )
    (net (code "95") (name "unconnected-(Arduino_Mega-PadAD14)") (class "Default")
      (node (ref "Arduino_Mega") (pin "AD14") (pinfunction "AD14_AD14") (pintype "passive"))
    )
    (net (code "96") (name "unconnected-(Arduino_Mega-PadAD15)") (class "Default")
      (node (ref "Arduino_Mega") (pin "AD15") (pinfunction "AD15_AD15") (pintype "passive"))
    )
    (net (code "97") (name "unconnected-(Arduino_Mega-PadAREF)") (class "Default")
      (node (ref "Arduino_Mega") (pin "AREF") (pinfunction "AREF_AREF") (pintype "passive"))
    )
    (net (code "98") (name "unconnected-(Arduino_Mega-PadIOREF)") (class "Default")
      (node (ref "Arduino_Mega") (pin "IOREF") (pinfunction "IOREF_IOREF") (pintype "passive"))
    )
    (net (code "99") (name "unconnected-(Arduino_Mega-PadNC)") (class "Default")
      (node (ref "Arduino_Mega") (pin "NC") (pinfunction "NC_NC") (pintype "passive"))
    )
    (net (code "100") (name "unconnected-(Arduino_Mega-PadRESET)") (class "Default")
      (node (ref "Arduino_Mega") (pin "RESET") (pinfunction "RESET_RESET") (pintype "passive"))
    )
    (net (code "101") (name "unconnected-(Arduino_Switch-Pin_3-Pad3)") (class "Default")
      (node (ref "Arduino_Switch") (pin "3") (pinfunction "Pin_3_3") (pintype "power_in"))
    )
    (net (code "102") (name "unconnected-(Bluetooth-Enable-Pad1)") (class "Default")
      (node (ref "Bluetooth") (pin "1") (pinfunction "Enable_1") (pintype "passive"))
    )
    (net (code "103") (name "unconnected-(Bluetooth-State-Pad6)") (class "Default")
      (node (ref "Bluetooth") (pin "6") (pinfunction "State_6") (pintype "passive"))
    )
    (net (code "104") (name "unconnected-(Colour_Sensor-OE-Pad6)") (class "Default")
      (node (ref "Colour_Sensor") (pin "6") (pinfunction "OE_6") (pintype "passive"))
    )
    (net (code "105") (name "unconnected-(Colour_Sensor_Switch-Pin_3-Pad3)") (class "Default")
      (node (ref "Colour_Sensor_Switch") (pin "3") (pinfunction "Pin_3_3") (pintype "power_in"))
    )
    (net (code "106") (name "unconnected-(Gyro-ADO-Pad7)") (class "Default")
      (node (ref "Gyro") (pin "7") (pinfunction "ADO_7") (pintype "passive"))
    )
    (net (code "107") (name "unconnected-(Gyro-XCA-Pad6)") (class "Default")
      (node (ref "Gyro") (pin "6") (pinfunction "XCA_6") (pintype "passive"))
    )
    (net (code "108") (name "unconnected-(Gyro-XDA-Pad5)") (class "Default")
      (node (ref "Gyro") (pin "5") (pinfunction "XDA_5") (pintype "passive"))
    )
    (net (code "109") (name "unconnected-(NRF-IRQ-Pad8)") (class "Default")
      (node (ref "NRF") (pin "8") (pinfunction "IRQ_8") (pintype "passive"))
    )
    (net (code "110") (name "unconnected-(Reykha_IR_Panel-D0-Pad4)") (class "Default")
      (node (ref "Reykha_IR_Panel") (pin "4") (pinfunction "D0_4") (pintype "passive"))
    )
    (net (code "111") (name "unconnected-(Reykha_IR_Panel-D1-Pad6)") (class "Default")
      (node (ref "Reykha_IR_Panel") (pin "6") (pinfunction "D1_6") (pintype "passive"))
    )
    (net (code "112") (name "unconnected-(Reykha_IR_Panel-D2-Pad8)") (class "Default")
      (node (ref "Reykha_IR_Panel") (pin "8") (pinfunction "D2_8") (pintype "passive"))
    )
    (net (code "113") (name "unconnected-(Reykha_IR_Panel-D3-Pad10)") (class "Default")
      (node (ref "Reykha_IR_Panel") (pin "10") (pinfunction "D3_10") (pintype "passive"))
    )
    (net (code "114") (name "unconnected-(Reykha_IR_Panel-D4-Pad12)") (class "Default")
      (node (ref "Reykha_IR_Panel") (pin "12") (pinfunction "D4_12") (pintype "passive"))
    )
    (net (code "115") (name "unconnected-(Reykha_IR_Panel-D5-Pad14)") (class "Default")
      (node (ref "Reykha_IR_Panel") (pin "14") (pinfunction "D5_14") (pintype "passive"))
    )
    (net (code "116") (name "unconnected-(Reykha_IR_Panel-D6-Pad16)") (class "Default")
      (node (ref "Reykha_IR_Panel") (pin "16") (pinfunction "D6_16") (pintype "passive"))
    )
    (net (code "117") (name "unconnected-(Reykha_IR_Panel-D7-Pad18)") (class "Default")
      (node (ref "Reykha_IR_Panel") (pin "18") (pinfunction "D7_18") (pintype "passive"))
    )
    (net (code "118") (name "unconnected-(Reykha_Switch-Pin_3-Pad3)") (class "Default")
      (node (ref "Reykha_Switch") (pin "3") (pinfunction "Pin_3_3") (pintype "power_in"))
    )
    (net (code "119") (name "unconnected-(ToF_1-GPIO-Pad3)") (class "Default")
      (node (ref "ToF_1") (pin "3") (pinfunction "GPIO_3") (pintype "passive"))
    )
    (net (code "120") (name "unconnected-(ToF_2-GPIO-Pad3)") (class "Default")
      (node (ref "ToF_2") (pin "3") (pinfunction "GPIO_3") (pintype "passive"))
    )
    (net (code "121") (name "unconnected-(ToF_3-GPIO-Pad3)") (class "Default")
      (node (ref "ToF_3") (pin "3") (pinfunction "GPIO_3") (pintype "passive"))
    )
    (net (code "122") (name "unconnected-(ToF_4-GPIO-Pad3)") (class "Default")
      (node (ref "ToF_4") (pin "3") (pinfunction "GPIO_3") (pintype "passive"))
    )
  )
)
